# PA_Transmitter_1LD_ExtVoltage.net
KiCad netlist of a schematic drawn in Altium Designer
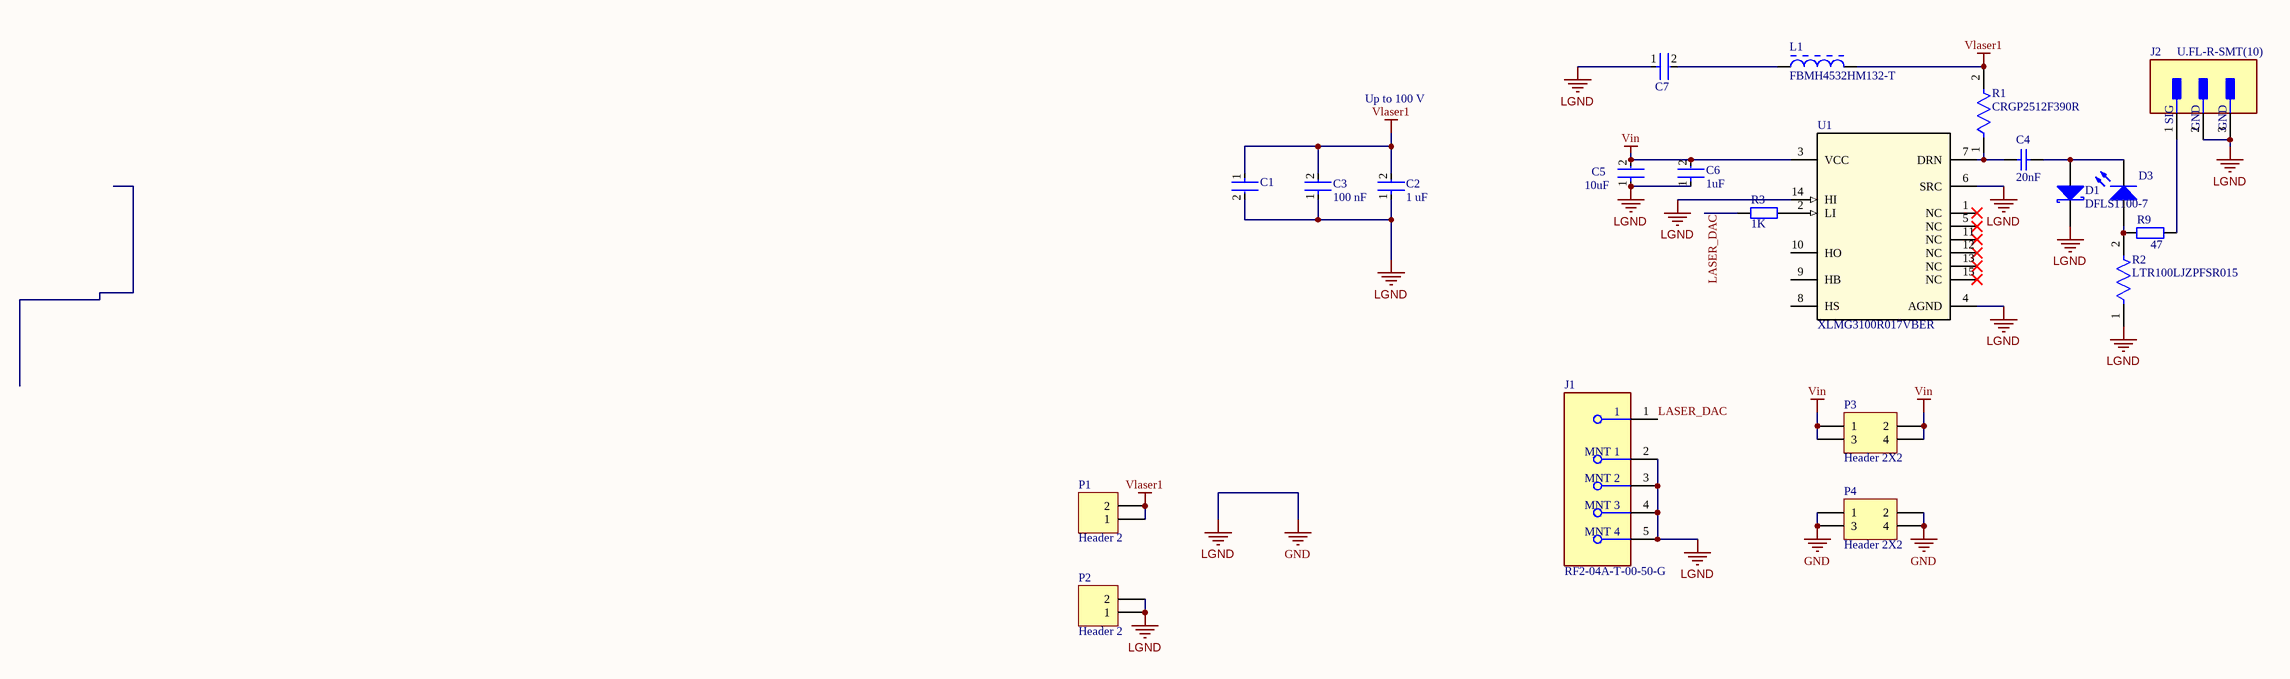
[diagram p0: PA_Transmitter_1LD_ExtVoltage.SchDoc]

(export (version "E")
  (design (tool "Eeschema 10.0.6"))
  (components
    (comp (ref "C1")
      (value "CC1210KKX7R9BB105")
      (footprint "FP-CC1210-GA-MFG")
      (description "Cap Ceramic 1uF 50V X7R 10% SMD 1210 125C T/R")
      (fields (field (name "MANUFACTURER") "Yageo"))
      (libsource (lib "Altium Content Vault") (part "11868f565c42a9108669ba33697ecf6"))
    )
    (comp (ref "C2")
      (value "1 uF")
      (footprint "FP-CL31B106KBHNNNE-MFG")
      (description "CAP CER 10UF 50V X7R 1206")
      (fields (field (name "MANUFACTURER") "Samsung") (field (name "TOLERANCE") "10%"))
      (libsource (lib "Altium Content Vault") (part "b4654b650e69147ec39a6b967a45e02"))
    )
    (comp (ref "C3")
      (value "100 nF")
      (footprint "FP-CL31B106KBHNNNE-MFG")
      (description "CAP CER 10UF 50V X7R 1206")
      (fields (field (name "MANUFACTURER") "Samsung") (field (name "TOLERANCE") "10%"))
      (libsource (lib "Altium Content Vault") (part "b4654b650e69147ec39a6b967a45e02"))
    )
    (comp (ref "C4")
      (value "20nF")
      (footprint "RESC2013X60X35ML10T20")
      (description "Chip capacitor")
      (fields (field (name "VOLTAGE") "50V"))
      (libsource (lib "MyLibSch") (part "CC0805"))
    )
    (comp (ref "C5")
      (value "10uF")
      (footprint "FP-CL31B106KBHNNNE-MFG")
      (description "CAP CER 10UF 50V X7R 1206")
      (fields (field (name "MANUFACTURER") "Samsung") (field (name "TOLERANCE") "10%"))
      (libsource (lib "Altium Content Vault") (part "b4654b650e69147ec39a6b967a45e02"))
    )
    (comp (ref "C6")
      (value "1uF")
      (footprint "FP-CL31B106KBHNNNE-MFG")
      (description "CAP CER 10UF 50V X7R 1206")
      (fields (field (name "MANUFACTURER") "Samsung") (field (name "TOLERANCE") "10%"))
      (libsource (lib "Altium Content Vault") (part "b4654b650e69147ec39a6b967a45e02"))
    )
    (comp (ref "C7")
      (value "CC1210KKX7R9BB105")
      (footprint "FP-CC1210-GA-MFG")
      (description "Cap Ceramic 1uF 50V X7R 10% SMD 1210 125C T/R")
      (fields (field (name "MANUFACTURER") "Yageo"))
      (libsource (lib "Altium Content Vault") (part "11868f565c42a9108669ba33697ecf6"))
    )
    (comp (ref "D1")
      (value "DFLS1100-7")
      (footprint "DIOD-POWERDI123-2_V")
      (fields (field (name "MANUFACTURER") "Diodes Inc"))
      (libsource (lib "Altium Content Vault") (part "DSKY-AK-2"))
    )
    (comp (ref "D3")
      (value "Light-Emitting Diode")
      (footprint "FP-DPGEW1S09H-MFG")
      (libsource (lib "Simulation Generic Components") (part "LED"))
    )
    (comp (ref "J1")
      (value "RF2-04A-T-00-50-G")
      (footprint "FP-RF2-04A-T-00-50-G-MFG")
      (description "CONN SMA JACK STR 50 OHM PCB")
      (libsource (lib "Altium Content Vault") (part "c65b8a639cdaef1819ea20b5466f8fa"))
    )
    (comp (ref "J2")
      (value "U.FL-R-SMT(10)")
      (footprint "FP-U_FL-R-SMT_10-MFG")
      (description "CONN U.FL RCPT STR 50 OHM SMD")
      (libsource (lib "Altium Content Vault") (part "eef6fde44c591823e8076210edfe12f"))
    )
    (comp (ref "L1")
      (value "FBMH4532HM132-T")
      (footprint "TAYO-FBMH4532-2_V")
      (description "None")
      (fields (field (name "TOLERANCE") "25%"))
      (libsource (lib "Altium Content Vault") (part "TAYO-IND_FB-2"))
    )
    (comp (ref "P1")
      (value "Header 2")
      (footprint "HDR1X2")
      (description "Header, 2-Pin")
      (fields (field (name "PUBLISHER") "Altium Limited"))
      (libsource (lib "Miscellaneous Connectors") (part "Header 2"))
    )
    (comp (ref "P2")
      (value "Header 2")
      (footprint "HDR1X2")
      (description "Header, 2-Pin")
      (fields (field (name "PUBLISHER") "Altium Limited"))
      (libsource (lib "Miscellaneous Connectors") (part "Header 2"))
    )
    (comp (ref "P3")
      (value "Header 2X2")
      (footprint "HDR2X2")
      (description "Header, 2-Pin, Dual row")
      (fields (field (name "PUBLISHER") "Altium Limited"))
      (libsource (lib "Miscellaneous Connectors") (part "Header 2X2"))
    )
    (comp (ref "P4")
      (value "Header 2X2")
      (footprint "HDR2X2")
      (description "Header, 2-Pin, Dual row")
      (fields (field (name "PUBLISHER") "Altium Limited"))
      (libsource (lib "Miscellaneous Connectors") (part "Header 2X2"))
    )
    (comp (ref "R1")
      (value "CRGP2512F390R")
      (footprint "FP-CRGP2512-IPC_C")
      (description "CRGP 2512 390R 1%")
      (fields (field (name "TOLERANCE") "0.01") (field (name "MANUFACTURER") "TE"))
      (libsource (lib "Altium Content Vault") (part "1029c3af85768c4190bb7ad29bc67b5"))
    )
    (comp (ref "R2")
      (value "LTR100LJZPFSR015")
      (footprint "FP-LTR100L-MFG")
      (description "LTR100LJZPFSR015 Res 0.015 Ohm 1% 4W 2512 Wide")
      (fields (field (name "TOLERANCE") "1%"))
      (libsource (lib "Altium Content Vault") (part "1029c3af85768c4190bb7ad29bc67b5"))
    )
    (comp (ref "R3")
      (value "1K")
      (footprint "RESC2013X60X35ML10T20")
      (description "Chip resistor")
      (fields (field (name "TOLERANCE") "5%"))
      (libsource (lib "") (part "RC0805_1"))
    )
    (comp (ref "R9")
      (value "47")
      (footprint "RESC2013X60X35ML10T20")
      (description "Chip resistor")
      (fields (field (name "TOLERANCE") "5%"))
      (libsource (lib "MyLibSch") (part "RC0805"))
    )
    (comp (ref "U1")
      (value "XLMG3100R017VBER")
      (footprint "VBE0015A-MFG")
      (description "No Description Available")
      (libsource (lib "XLMG3100R017VBER") (part "XLMG3100R017VBER"))
    )
  )
  (nets
    (net (code "1") (name "/LASER_DAC") (class "Default")
      (node (ref "J1") (pin "1") (pinfunction "1_1") (pintype "passive"))
      (node (ref "R3") (pin "2") (pinfunction "2_2") (pintype "passive"))
    )
    (net (code "2") (name "GND") (class "Default")
      (node (ref "C1") (pin "2") (pinfunction "2_2") (pintype "passive"))
      (node (ref "C2") (pin "1") (pinfunction "1_1") (pintype "passive"))
      (node (ref "C3") (pin "1") (pinfunction "1_1") (pintype "passive"))
      (node (ref "C5") (pin "1") (pinfunction "1_1") (pintype "passive"))
      (node (ref "C6") (pin "1") (pinfunction "1_1") (pintype "passive"))
      (node (ref "C7") (pin "1") (pinfunction "1_1") (pintype "passive"))
      (node (ref "D1") (pin "2") (pinfunction "K_2") (pintype "passive"))
      (node (ref "J1") (pin "2") (pinfunction "MNT_1_2") (pintype "passive"))
      (node (ref "J1") (pin "3") (pinfunction "MNT_2_3") (pintype "passive"))
      (node (ref "J1") (pin "4") (pinfunction "MNT_3_4") (pintype "passive"))
      (node (ref "J1") (pin "5") (pinfunction "MNT_4_5") (pintype "passive"))
      (node (ref "J2") (pin "2") (pinfunction "GND_2") (pintype "power_in"))
      (node (ref "J2") (pin "3") (pinfunction "GND_3") (pintype "power_in"))
      (node (ref "P2") (pin "1") (pinfunction "1_1") (pintype "passive"))
      (node (ref "P2") (pin "2") (pinfunction "2_2") (pintype "passive"))
      (node (ref "P4") (pin "1") (pinfunction "1_1") (pintype "passive"))
      (node (ref "P4") (pin "2") (pinfunction "2_2") (pintype "passive"))
      (node (ref "P4") (pin "3") (pinfunction "3_3") (pintype "passive"))
      (node (ref "P4") (pin "4") (pinfunction "4_4") (pintype "passive"))
      (node (ref "R2") (pin "1") (pinfunction "1_1") (pintype "passive"))
      (node (ref "U1") (pin "14") (pinfunction "HI_14") (pintype "input"))
      (node (ref "U1") (pin "4") (pinfunction "AGND_4") (pintype "power_in"))
      (node (ref "U1") (pin "6") (pinfunction "SRC_6") (pintype "passive"))
    )
    (net (code "3") (name "Net-(C7-Pad2)") (class "Default")
      (node (ref "C7") (pin "2") (pinfunction "2_2") (pintype "passive"))
      (node (ref "L1") (pin "1") (pinfunction "1_1") (pintype "passive"))
    )
    (net (code "4") (name "Net-(D1-A)") (class "Default")
      (node (ref "C4") (pin "1") (pinfunction "1_1") (pintype "passive"))
      (node (ref "D1") (pin "1") (pinfunction "A_1") (pintype "passive"))
      (node (ref "D3") (pin "2") (pinfunction "K_2") (pintype "passive"))
    )
    (net (code "5") (name "Net-(D3-A)") (class "Default")
      (node (ref "D3") (pin "1") (pinfunction "A_1") (pintype "passive"))
      (node (ref "R2") (pin "2") (pinfunction "2_2") (pintype "passive"))
      (node (ref "R9") (pin "1") (pinfunction "1_1") (pintype "passive"))
    )
    (net (code "6") (name "Net-(J2-SIG)") (class "Default")
      (node (ref "J2") (pin "1") (pinfunction "SIG_1") (pintype "passive"))
      (node (ref "R9") (pin "2") (pinfunction "2_2") (pintype "passive"))
    )
    (net (code "7") (name "Net-(U1-DRN)") (class "Default")
      (node (ref "C4") (pin "2") (pinfunction "2_2") (pintype "passive"))
      (node (ref "R1") (pin "1") (pinfunction "1_1") (pintype "passive"))
      (node (ref "U1") (pin "7") (pinfunction "DRN_7") (pintype "passive"))
    )
    (net (code "8") (name "Net-(U1-LI)") (class "Default")
      (node (ref "R3") (pin "1") (pinfunction "1_1") (pintype "passive"))
      (node (ref "U1") (pin "2") (pinfunction "LI_2") (pintype "input"))
    )
    (net (code "9") (name "Vin") (class "Default")
      (node (ref "C5") (pin "2") (pinfunction "2_2") (pintype "passive"))
      (node (ref "C6") (pin "2") (pinfunction "2_2") (pintype "passive"))
      (node (ref "P3") (pin "1") (pinfunction "1_1") (pintype "passive"))
      (node (ref "P3") (pin "2") (pinfunction "2_2") (pintype "passive"))
      (node (ref "P3") (pin "3") (pinfunction "3_3") (pintype "passive"))
      (node (ref "P3") (pin "4") (pinfunction "4_4") (pintype "passive"))
      (node (ref "U1") (pin "3") (pinfunction "VCC_3") (pintype "power_in"))
    )
    (net (code "10") (name "Vlaser1") (class "Default")
      (node (ref "C1") (pin "1") (pinfunction "1_1") (pintype "passive"))
      (node (ref "C2") (pin "2") (pinfunction "2_2") (pintype "passive"))
      (node (ref "C3") (pin "2") (pinfunction "2_2") (pintype "passive"))
      (node (ref "L1") (pin "2") (pinfunction "2_2") (pintype "passive"))
      (node (ref "P1") (pin "1") (pinfunction "1_1") (pintype "passive"))
      (node (ref "P1") (pin "2") (pinfunction "2_2") (pintype "passive"))
      (node (ref "R1") (pin "2") (pinfunction "2_2") (pintype "passive"))
    )
    (net (code "11") (name "unconnected-(U1-HB-Pad9)") (class "Default")
      (node (ref "U1") (pin "9") (pinfunction "HB_9") (pintype "passive"))
    )
    (net (code "12") (name "unconnected-(U1-HO-Pad10)") (class "Default")
      (node (ref "U1") (pin "10") (pinfunction "HO_10") (pintype "passive"))
    )
    (net (code "13") (name "unconnected-(U1-HS-Pad8)") (class "Default")
      (node (ref "U1") (pin "8") (pinfunction "HS_8") (pintype "passive"))
    )
    (net (code "14") (name "unconnected-(U1-NC-Pad1)") (class "Default")
      (node (ref "U1") (pin "1") (pinfunction "NC_1") (pintype "passive+no_connect"))
    )
    (net (code "15") (name "unconnected-(U1-NC-Pad5)") (class "Default")
      (node (ref "U1") (pin "5") (pinfunction "NC_5") (pintype "passive+no_connect"))
    )
    (net (code "16") (name "unconnected-(U1-NC-Pad11)") (class "Default")
      (node (ref "U1") (pin "11") (pinfunction "NC_11") (pintype "passive+no_connect"))
    )
    (net (code "17") (name "unconnected-(U1-NC-Pad12)") (class "Default")
      (node (ref "U1") (pin "12") (pinfunction "NC_12") (pintype "passive+no_connect"))
    )
    (net (code "18") (name "unconnected-(U1-NC-Pad13)") (class "Default")
      (node (ref "U1") (pin "13") (pinfunction "NC_13") (pintype "passive+no_connect"))
    )
    (net (code "19") (name "unconnected-(U1-NC-Pad15)") (class "Default")
      (node (ref "U1") (pin "15") (pinfunction "NC_15") (pintype "passive+no_connect"))
    )
  )
)
